# CAN_Transceiver.net
KiCad netlist of a schematic drawn in Altium Designer
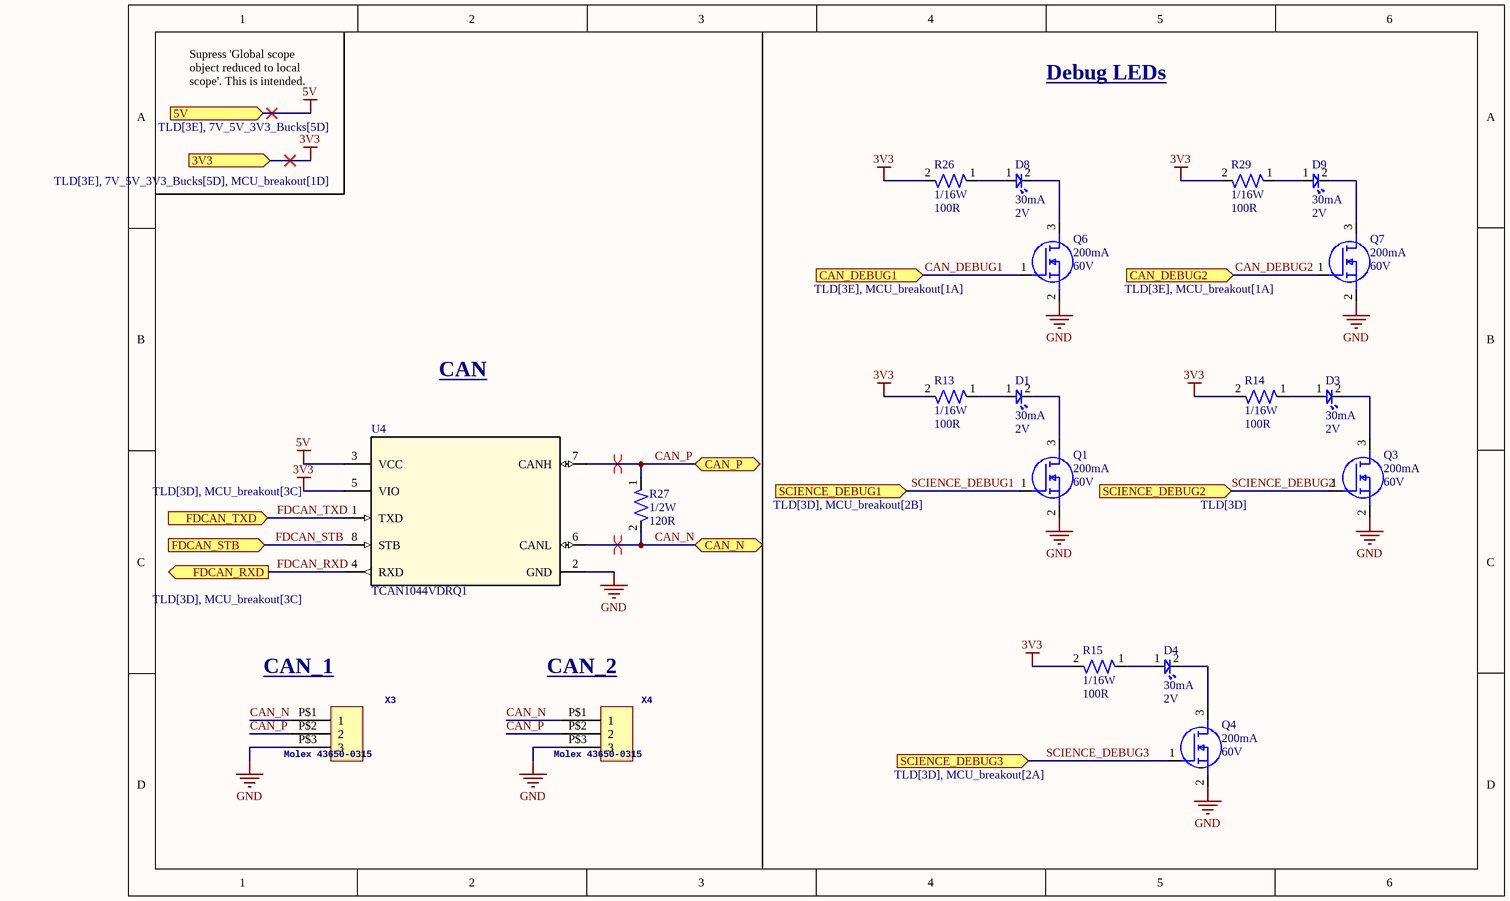
[diagram p0: CAN_Transceiver.SchDoc]

(export (version "E")
  (design (tool "Eeschema 10.0.6"))
  (components
    (comp (ref "D1")
      (value "BL-HKC36G-AV-TRB")
      (footprint "LED-0603")
      (description "LED YELLOW CLEAR 0603 SMD")
      (fields (field (name "FORWARD CURRENT") "30mA") (field (name "FORWARD VOLTAGE") "2V"))
      (libsource (lib "JLC_25") (part "LED-0001"))
    )
    (comp (ref "D3")
      (value "BL-HKC36G-AV-TRB")
      (footprint "LED-0603")
      (description "LED YELLOW CLEAR 0603 SMD")
      (fields (field (name "FORWARD CURRENT") "30mA") (field (name "FORWARD VOLTAGE") "2V"))
      (libsource (lib "JLC_25") (part "LED-0001"))
    )
    (comp (ref "D4")
      (value "BL-HKC36G-AV-TRB")
      (footprint "LED-0603")
      (description "LED YELLOW CLEAR 0603 SMD")
      (fields (field (name "FORWARD CURRENT") "30mA") (field (name "FORWARD VOLTAGE") "2V"))
      (libsource (lib "JLC_25") (part "LED-0001"))
    )
    (comp (ref "D8")
      (value "BL-HKC36G-AV-TRB")
      (footprint "LED-0603")
      (description "LED YELLOW CLEAR 0603 SMD")
      (fields (field (name "FORWARD CURRENT") "30mA") (field (name "FORWARD VOLTAGE") "2V"))
      (libsource (lib "JLC_25") (part "LED-0001"))
    )
    (comp (ref "D9")
      (value "BL-HKC36G-AV-TRB")
      (footprint "LED-0603")
      (description "LED YELLOW CLEAR 0603 SMD")
      (fields (field (name "FORWARD CURRENT") "30mA") (field (name "FORWARD VOLTAGE") "2V"))
      (libsource (lib "JLC_25") (part "LED-0001"))
    )
    (comp (ref "Q1")
      (value "T2N7002AK,LM")
      (footprint "IC-SOT23-3")
      (description "MOSFET N-CH 60V 200MA SOT23")
      (fields (field (name "CONTINUOUS CURRENT") "200mA") (field (name "VOLTAGE") "60V"))
      (libsource (lib "JLC_25") (part "NMOS-200MA-0001"))
    )
    (comp (ref "Q3")
      (value "T2N7002AK,LM")
      (footprint "IC-SOT23-3")
      (description "MOSFET N-CH 60V 200MA SOT23")
      (fields (field (name "CONTINUOUS CURRENT") "200mA") (field (name "VOLTAGE") "60V"))
      (libsource (lib "JLC_25") (part "NMOS-200MA-0001"))
    )
    (comp (ref "Q4")
      (value "T2N7002AK,LM")
      (footprint "IC-SOT23-3")
      (description "MOSFET N-CH 60V 200MA SOT23")
      (fields (field (name "CONTINUOUS CURRENT") "200mA") (field (name "VOLTAGE") "60V"))
      (libsource (lib "JLC_25") (part "NMOS-200MA-0001"))
    )
    (comp (ref "Q6")
      (value "T2N7002AK,LM")
      (footprint "IC-SOT23-3")
      (description "MOSFET N-CH 60V 200MA SOT23")
      (fields (field (name "CONTINUOUS CURRENT") "200mA") (field (name "VOLTAGE") "60V"))
      (libsource (lib "JLC_25") (part "NMOS-200MA-0001"))
    )
    (comp (ref "Q7")
      (value "T2N7002AK,LM")
      (footprint "IC-SOT23-3")
      (description "MOSFET N-CH 60V 200MA SOT23")
      (fields (field (name "CONTINUOUS CURRENT") "200mA") (field (name "VOLTAGE") "60V"))
      (libsource (lib "JLC_25") (part "NMOS-200MA-0001"))
    )
    (comp (ref "R13")
      (value "RC0402FR-07100RL")
      (footprint "RES-0402")
      (description "RES 100 OHM 1% 1/16W 0402")
      (fields
        (field (name "TOLERANCE") "1%")
        (field (name "POWER") "1/16W")
        (field (name "RESISTANCE") "100R")
      )
      (libsource (lib "JLC_25") (part "RES-100-0001"))
    )
    (comp (ref "R14")
      (value "RC0402FR-07100RL")
      (footprint "RES-0402")
      (description "RES 100 OHM 1% 1/16W 0402")
      (fields
        (field (name "TOLERANCE") "1%")
        (field (name "POWER") "1/16W")
        (field (name "RESISTANCE") "100R")
      )
      (libsource (lib "JLC_25") (part "RES-100-0001"))
    )
    (comp (ref "R15")
      (value "RC0402FR-07100RL")
      (footprint "RES-0402")
      (description "RES 100 OHM 1% 1/16W 0402")
      (fields
        (field (name "TOLERANCE") "1%")
        (field (name "POWER") "1/16W")
        (field (name "RESISTANCE") "100R")
      )
      (libsource (lib "JLC_25") (part "RES-100-0001"))
    )
    (comp (ref "R26")
      (value "RC0402FR-07100RL")
      (footprint "RES-0402")
      (description "RES 100 OHM 1% 1/16W 0402")
      (fields
        (field (name "TOLERANCE") "1%")
        (field (name "POWER") "1/16W")
        (field (name "RESISTANCE") "100R")
      )
      (libsource (lib "JLC_25") (part "RES-100-0001"))
    )
    (comp (ref "R27")
      (value "RC1210FR-07120RL")
      (footprint "RES-1210")
      (description "RES 120 OHM 1% 1/2W 1210")
      (fields
        (field (name "TOLERANCE") "1%")
        (field (name "POWER") "1/2W")
        (field (name "RESISTANCE") "120R")
      )
      (libsource (lib "JLC_25") (part "RES-120-0001"))
    )
    (comp (ref "R29")
      (value "RC0402FR-07100RL")
      (footprint "RES-0402")
      (description "RES 100 OHM 1% 1/16W 0402")
      (fields
        (field (name "TOLERANCE") "1%")
        (field (name "POWER") "1/16W")
        (field (name "RESISTANCE") "100R")
      )
      (libsource (lib "JLC_25") (part "RES-100-0001"))
    )
    (comp (ref "U4")
      (value "TCAN1044VDRQ1")
      (footprint "IC-8SOIC")
      (description "IC TRANSCEIVER 1/1 8SOIC")
      (libsource (lib "JLC_25") (part "IC-CAN-0001"))
    )
    (comp (ref "X3")
      (value "Molex 43650-0315")
      (footprint "43650-0315")
      (libsource (lib "JLC_25") (part "Micro-Fit Molex 3 Pin Vertical"))
    )
    (comp (ref "X4")
      (value "Molex 43650-0315")
      (footprint "43650-0315")
      (libsource (lib "JLC_25") (part "Micro-Fit Molex 3 Pin Vertical"))
    )
  )
  (nets
    (net (code "1") (name "/CAN_DEBUG1") (class "Default")
      (node (ref "Q6") (pin "1") (pinfunction "G_1") (pintype "passive"))
    )
    (net (code "2") (name "/CAN_DEBUG2") (class "Default")
      (node (ref "Q7") (pin "1") (pinfunction "G_1") (pintype "passive"))
    )
    (net (code "3") (name "/CAN_N") (class "Default")
      (node (ref "R27") (pin "2") (pinfunction "2_2") (pintype "passive"))
      (node (ref "U4") (pin "6") (pinfunction "CANL_6") (pintype "bidirectional"))
      (node (ref "X3") (pin "P$1") (pinfunction "1_P$1") (pintype "passive"))
      (node (ref "X4") (pin "P$1") (pinfunction "1_P$1") (pintype "passive"))
    )
    (net (code "4") (name "/CAN_P") (class "Default")
      (node (ref "R27") (pin "1") (pinfunction "1_1") (pintype "passive"))
      (node (ref "U4") (pin "7") (pinfunction "CANH_7") (pintype "bidirectional"))
      (node (ref "X3") (pin "P$2") (pinfunction "2_P$2") (pintype "passive"))
      (node (ref "X4") (pin "P$2") (pinfunction "2_P$2") (pintype "passive"))
    )
    (net (code "5") (name "/FDCAN_RXD") (class "Default")
      (node (ref "U4") (pin "4") (pinfunction "RXD_4") (pintype "output"))
    )
    (net (code "6") (name "/FDCAN_STB") (class "Default")
      (node (ref "U4") (pin "8") (pinfunction "STB_8") (pintype "input"))
    )
    (net (code "7") (name "/FDCAN_TXD") (class "Default")
      (node (ref "U4") (pin "1") (pinfunction "TXD_1") (pintype "input"))
    )
    (net (code "8") (name "/SCIENCE_DEBUG1") (class "Default")
      (node (ref "Q1") (pin "1") (pinfunction "G_1") (pintype "passive"))
    )
    (net (code "9") (name "/SCIENCE_DEBUG2") (class "Default")
      (node (ref "Q3") (pin "1") (pinfunction "G_1") (pintype "passive"))
    )
    (net (code "10") (name "/SCIENCE_DEBUG3") (class "Default")
      (node (ref "Q4") (pin "1") (pinfunction "G_1") (pintype "passive"))
    )
    (net (code "11") (name "3V3") (class "Default")
      (node (ref "R13") (pin "2") (pinfunction "2_2") (pintype "passive"))
      (node (ref "R14") (pin "2") (pinfunction "2_2") (pintype "passive"))
      (node (ref "R15") (pin "2") (pinfunction "2_2") (pintype "passive"))
      (node (ref "R26") (pin "2") (pinfunction "2_2") (pintype "passive"))
      (node (ref "R29") (pin "2") (pinfunction "2_2") (pintype "passive"))
      (node (ref "U4") (pin "5") (pinfunction "VIO_5") (pintype "power_in"))
    )
    (net (code "12") (name "5V") (class "Default")
      (node (ref "U4") (pin "3") (pinfunction "VCC_3") (pintype "power_in"))
    )
    (net (code "13") (name "GND") (class "Default")
      (node (ref "Q1") (pin "2") (pinfunction "S_2") (pintype "passive"))
      (node (ref "Q3") (pin "2") (pinfunction "S_2") (pintype "passive"))
      (node (ref "Q4") (pin "2") (pinfunction "S_2") (pintype "passive"))
      (node (ref "Q6") (pin "2") (pinfunction "S_2") (pintype "passive"))
      (node (ref "Q7") (pin "2") (pinfunction "S_2") (pintype "passive"))
      (node (ref "U4") (pin "2") (pinfunction "GND_2") (pintype "power_in"))
      (node (ref "X3") (pin "P$3") (pinfunction "3_P$3") (pintype "passive"))
      (node (ref "X4") (pin "P$3") (pinfunction "3_P$3") (pintype "passive"))
    )
    (net (code "14") (name "Net-(D1-Pad1)") (class "Default")
      (node (ref "D1") (pin "1") (pinfunction "1_1") (pintype "passive"))
      (node (ref "R13") (pin "1") (pinfunction "1_1") (pintype "passive"))
    )
    (net (code "15") (name "Net-(D3-Pad1)") (class "Default")
      (node (ref "D3") (pin "1") (pinfunction "1_1") (pintype "passive"))
      (node (ref "R14") (pin "1") (pinfunction "1_1") (pintype "passive"))
    )
    (net (code "16") (name "Net-(D4-Pad1)") (class "Default")
      (node (ref "D4") (pin "1") (pinfunction "1_1") (pintype "passive"))
      (node (ref "R15") (pin "1") (pinfunction "1_1") (pintype "passive"))
    )
    (net (code "17") (name "Net-(D8-Pad1)") (class "Default")
      (node (ref "D8") (pin "1") (pinfunction "1_1") (pintype "passive"))
      (node (ref "R26") (pin "1") (pinfunction "1_1") (pintype "passive"))
    )
    (net (code "18") (name "Net-(D9-Pad1)") (class "Default")
      (node (ref "D9") (pin "1") (pinfunction "1_1") (pintype "passive"))
      (node (ref "R29") (pin "1") (pinfunction "1_1") (pintype "passive"))
    )
    (net (code "19") (name "Net-(Q1-D)") (class "Default")
      (node (ref "D1") (pin "2") (pinfunction "2_2") (pintype "passive"))
      (node (ref "Q1") (pin "3") (pinfunction "D_3") (pintype "passive"))
    )
    (net (code "20") (name "Net-(Q3-D)") (class "Default")
      (node (ref "D3") (pin "2") (pinfunction "2_2") (pintype "passive"))
      (node (ref "Q3") (pin "3") (pinfunction "D_3") (pintype "passive"))
    )
    (net (code "21") (name "Net-(Q4-D)") (class "Default")
      (node (ref "D4") (pin "2") (pinfunction "2_2") (pintype "passive"))
      (node (ref "Q4") (pin "3") (pinfunction "D_3") (pintype "passive"))
    )
    (net (code "22") (name "Net-(Q6-D)") (class "Default")
      (node (ref "D8") (pin "2") (pinfunction "2_2") (pintype "passive"))
      (node (ref "Q6") (pin "3") (pinfunction "D_3") (pintype "passive"))
    )
    (net (code "23") (name "Net-(Q7-D)") (class "Default")
      (node (ref "D9") (pin "2") (pinfunction "2_2") (pintype "passive"))
      (node (ref "Q7") (pin "3") (pinfunction "D_3") (pintype "passive"))
    )
  )
)
